# ST_LINK_V2-1.net
KiCad netlist of a schematic drawn in Altium Designer
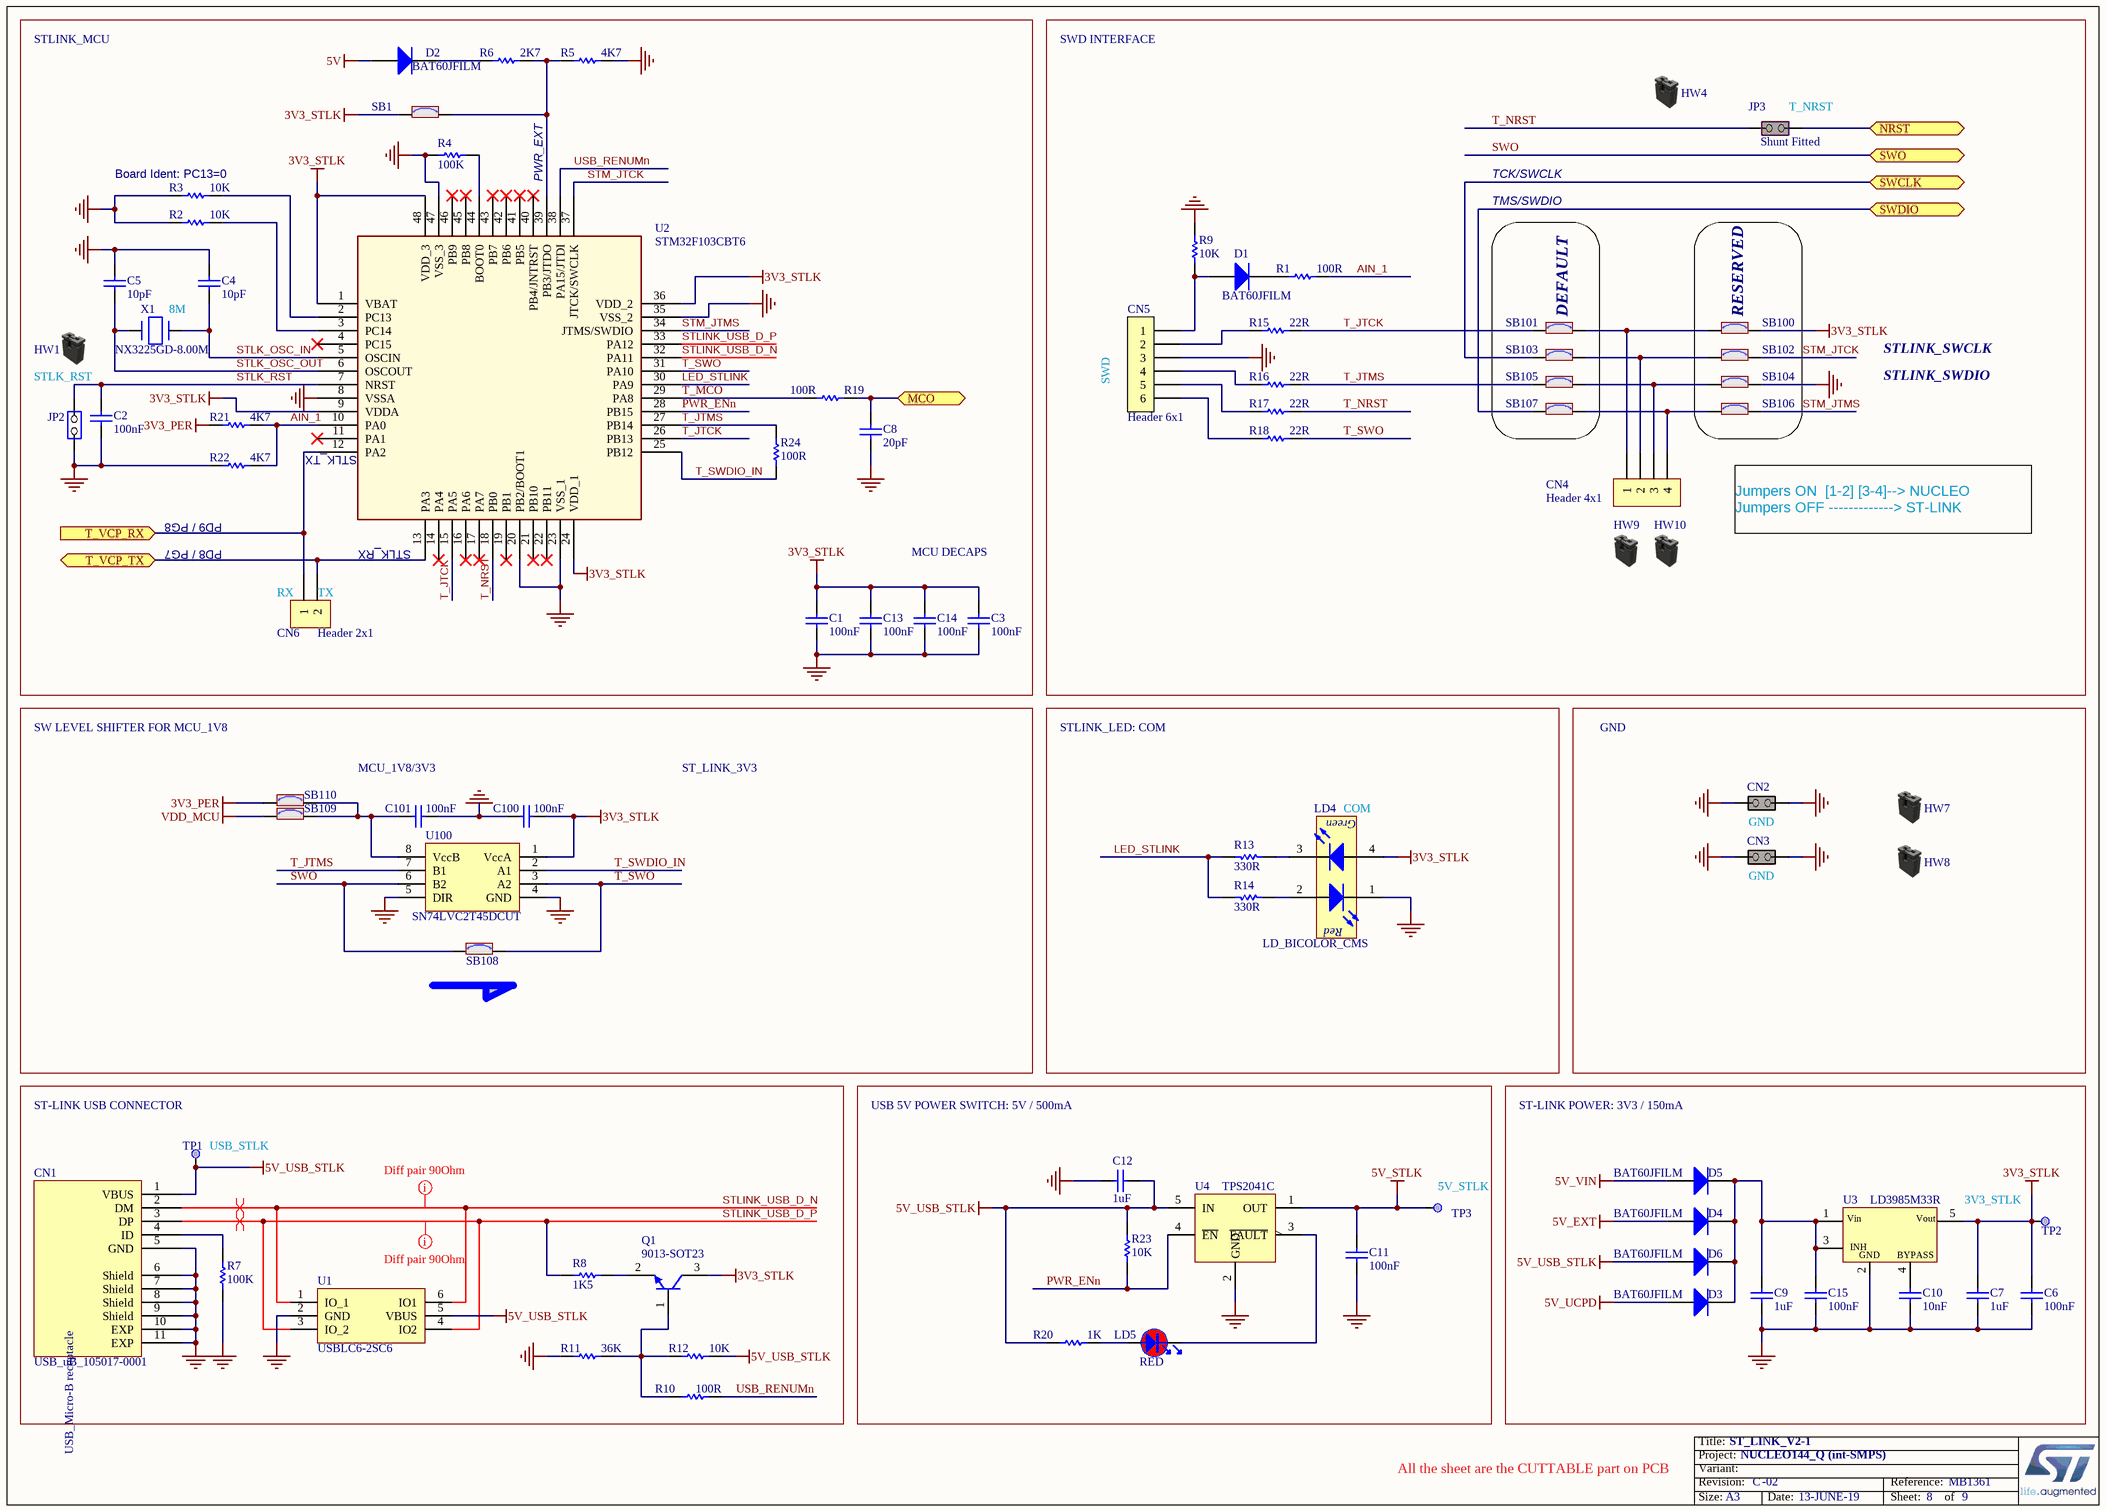
[diagram p0: ST_LINK_V2-1.SchDoc]

(export (version "E")
  (design (tool "Eeschema 10.0.6"))
  (components
    (comp (ref "C1")
      (value "100nF")
      (footprint "C0603")
      (description "Capacitor, MLCC, 100nF, 16V, X7R, 10%, 0603, T=0,8mm")
      (fields
        (field (name "INTERNAL_PART_NUMBER") "MCD-00211")
        (field (name "MANUFACTURER_PART_NUMBER") "CC0603KRX7R7BB104")
        (field (name "PROVIDED_BY") "Subcon")
      )
      (libsource (lib "MCD_PARTS_database") (part "Capacitor"))
    )
    (comp (ref "C2")
      (value "100nF")
      (footprint "C0603")
      (description "Capacitor, MLCC, 100nF, 16V, X7R, 10%, 0603, T=0,8mm")
      (fields
        (field (name "INTERNAL_PART_NUMBER") "MCD-00211")
        (field (name "MANUFACTURER_PART_NUMBER") "CC0603KRX7R7BB104")
        (field (name "PROVIDED_BY") "Subcon")
      )
      (libsource (lib "MCD_PARTS_database") (part "Capacitor"))
    )
    (comp (ref "C3")
      (value "100nF")
      (footprint "C0603")
      (description "Capacitor, MLCC, 100nF, 16V, X7R, 10%, 0603, T=0,8mm")
      (fields
        (field (name "INTERNAL_PART_NUMBER") "MCD-00211")
        (field (name "MANUFACTURER_PART_NUMBER") "CC0603KRX7R7BB104")
        (field (name "PROVIDED_BY") "Subcon")
      )
      (libsource (lib "MCD_PARTS_database") (part "Capacitor"))
    )
    (comp (ref "C4")
      (value "10pF")
      (footprint "C0402")
      (description "Capacitor, MLCC, 10pF, 50V, NPO, 5%, 0402, T=0,5mm")
      (fields
        (field (name "INTERNAL_PART_NUMBER") "MCD-00015")
        (field (name "MANUFACTURER_PART_NUMBER") "CC0402JRNPO9BN100")
        (field (name "PROVIDED_BY") "subcon")
      )
      (libsource (lib "MCD_PARTS_database") (part "Capacitor"))
    )
    (comp (ref "C5")
      (value "10pF")
      (footprint "C0402")
      (description "Capacitor, MLCC, 10pF, 50V, NPO, 5%, 0402, T=0,5mm")
      (fields
        (field (name "INTERNAL_PART_NUMBER") "MCD-00015")
        (field (name "MANUFACTURER_PART_NUMBER") "CC0402JRNPO9BN100")
        (field (name "PROVIDED_BY") "subcon")
      )
      (libsource (lib "MCD_PARTS_database") (part "Capacitor"))
    )
    (comp (ref "C6")
      (value "100nF")
      (footprint "C0603")
      (description "Capacitor, MLCC, 100nF, 16V, X7R, 10%, 0603, T=0,8mm")
      (fields
        (field (name "INTERNAL_PART_NUMBER") "MCD-00211")
        (field (name "MANUFACTURER_PART_NUMBER") "CC0603KRX7R7BB104")
        (field (name "PROVIDED_BY") "Subcon")
      )
      (libsource (lib "MCD_PARTS_database") (part "Capacitor"))
    )
    (comp (ref "C7")
      (value "1uF")
      (footprint "C0603")
      (description "Capacitor, MLCC, 1uF, 16V, X5R, 10%, 0603, T=0,8mm")
      (fields
        (field (name "INTERNAL_PART_NUMBER") "MCD-00010")
        (field (name "MANUFACTURER_PART_NUMBER") "CC0603KRX5R7BB105")
        (field (name "PROVIDED_BY") "SUBCO")
      )
      (libsource (lib "MCD_PARTS_database") (part "Capacitor"))
    )
    (comp (ref "C8")
      (value "20pF")
      (footprint "C0603")
      (description "Capacitor, MLCC, 20pF, 50V, NPO, 5%, 0603, T=0,8mm")
      (fields
        (field (name "INTERNAL_PART_NUMBER") "MCD-00638")
        (field (name "MANUFACTURER_PART_NUMBER") "CC0603JRNPO9BN200")
        (field (name "PROVIDED_BY") "Subcon")
      )
      (libsource (lib "MCD_PARTS_database") (part "Capacitor"))
    )
    (comp (ref "C9")
      (value "1uF")
      (footprint "C0603")
      (description "Capacitor, MLCC, 1uF, 16V, X5R, 10%, 0603, T=0,8mm")
      (fields
        (field (name "INTERNAL_PART_NUMBER") "MCD-00010")
        (field (name "MANUFACTURER_PART_NUMBER") "CC0603KRX5R7BB105")
        (field (name "PROVIDED_BY") "Subcon")
      )
      (libsource (lib "MCD_PARTS_database") (part "Capacitor"))
    )
    (comp (ref "C10")
      (value "10nF")
      (footprint "C0603")
      (description "Capacitor, MLCC, 10nF, 50V, X7R, 10%, 0603, T=0.8mm")
      (fields
        (field (name "INTERNAL_PART_NUMBER") "MCD-00017")
        (field (name "MANUFACTURER_PART_NUMBER") "CC0603KRX7R9BB103")
        (field (name "PROVIDED_BY") "Subcon")
      )
      (libsource (lib "MCD_PARTS_database") (part "Capacitor"))
    )
    (comp (ref "C11")
      (value "100nF")
      (footprint "C0603")
      (description "Capacitor, MLCC, 100nF, 16V, X7R, 10%, 0603, T=0,8mm")
      (fields
        (field (name "INTERNAL_PART_NUMBER") "MCD-00211")
        (field (name "MANUFACTURER_PART_NUMBER") "CC0603KRX7R7BB104")
        (field (name "PROVIDED_BY") "Subcon")
      )
      (libsource (lib "MCD_PARTS_database") (part "Capacitor"))
    )
    (comp (ref "C12")
      (value "1uF")
      (footprint "C0603")
      (description "Capacitor, MLCC, 1uF, 16V, X5R, 10%, 0603, T=0,8mm")
      (fields
        (field (name "INTERNAL_PART_NUMBER") "MCD-00010")
        (field (name "MANUFACTURER_PART_NUMBER") "CC0603KRX5R7BB105")
        (field (name "PROVIDED_BY") "SUBCO")
      )
      (libsource (lib "MCD_PARTS_database") (part "Capacitor"))
    )
    (comp (ref "C13")
      (value "100nF")
      (footprint "C0603")
      (description "Capacitor, MLCC, 100nF, 16V, X7R, 10%, 0603, T=0,8mm")
      (fields
        (field (name "INTERNAL_PART_NUMBER") "MCD-00211")
        (field (name "MANUFACTURER_PART_NUMBER") "CC0603KRX7R7BB104")
        (field (name "PROVIDED_BY") "Subcon")
      )
      (libsource (lib "MCD_PARTS_database") (part "Capacitor"))
    )
    (comp (ref "C14")
      (value "100nF")
      (footprint "C0603")
      (description "Capacitor, MLCC, 100nF, 16V, X7R, 10%, 0603, T=0,8mm")
      (fields
        (field (name "INTERNAL_PART_NUMBER") "MCD-00211")
        (field (name "MANUFACTURER_PART_NUMBER") "CC0603KRX7R7BB104")
        (field (name "PROVIDED_BY") "Subcon")
      )
      (libsource (lib "MCD_PARTS_database") (part "Capacitor"))
    )
    (comp (ref "C15")
      (value "100nF")
      (footprint "C0603")
      (description "Capacitor, MLCC, 100nF, 16V, X7R, 10%, 0603, T=0,8mm")
      (fields
        (field (name "INTERNAL_PART_NUMBER") "MCD-00211")
        (field (name "MANUFACTURER_PART_NUMBER") "CC0603KRX7R7BB104")
        (field (name "PROVIDED_BY") "Subcon")
      )
      (libsource (lib "MCD_PARTS_database") (part "Capacitor"))
    )
    (comp (ref "C100")
      (value "100nF")
      (footprint "C0603")
      (description "Capacitor, MLCC, 100nF, 16V, X7R, 10%, 0603, T=0,8mm")
      (fields
        (field (name "INTERNAL_PART_NUMBER") "MCD-00211")
        (field (name "MANUFACTURER_PART_NUMBER") "CC0603KRX7R7BB104")
        (field (name "PROVIDED_BY") "Subcon")
      )
      (libsource (lib "MCD_PARTS_database") (part "Capacitor"))
    )
    (comp (ref "C101")
      (value "100nF")
      (footprint "C0603")
      (description "Capacitor, MLCC, 100nF, 16V, X7R, 10%, 0603, T=0,8mm")
      (fields
        (field (name "INTERNAL_PART_NUMBER") "MCD-00211")
        (field (name "MANUFACTURER_PART_NUMBER") "CC0603KRX7R7BB104")
        (field (name "PROVIDED_BY") "Subcon")
      )
      (libsource (lib "MCD_PARTS_database") (part "Capacitor"))
    )
    (comp (ref "CN1")
      (value "USB_uB_105017-0001")
      (footprint "CON_USBMICROB_MOLEX_105017-0001_H2P90")
      (description "USB-MICRO-B, 0.65mm, RA, SMT, Bottom Mount,")
      (fields
        (field (name "INTERNAL_PART_NUMBER") "MCD-00028")
        (field (name "MANUFACTURER_PART_NUMBER") "1050170001")
        (field (name "PROVIDED_BY") "Subcon")
      )
      (libsource (lib "MCD_PARTS_database") (part "USB_uB_105017.0001"))
    )
    (comp (ref "CN2")
      (value "~")
      (footprint "CON_SAMTEC_TSW-102-09-X-S")
      (description "Header, 2x1, 2,54mm, VR, TH, Height 5.84mm/10.16mm")
      (fields
        (field (name "INTERNAL_PART_NUMBER") "MCD-00214")
        (field (name "MANUFACTURER_PART_NUMBER") "TSW-102-09-x-S")
        (field (name "PROVIDED_BY") "Subcon")
      )
      (libsource (lib "MCD_PARTS_database") (part "Jumper_Header 2x1"))
    )
    (comp (ref "CN3")
      (value "~")
      (footprint "CON_SAMTEC_TSW-102-09-X-S")
      (description "Header, 2x1, 2,54mm, VR, TH, Height 5.84mm/10.16mm")
      (fields
        (field (name "INTERNAL_PART_NUMBER") "MCD-00214")
        (field (name "MANUFACTURER_PART_NUMBER") "TSW-102-09-x-S")
        (field (name "PROVIDED_BY") "Subcon")
      )
      (libsource (lib "MCD_PARTS_database") (part "Jumper_Header 2x1"))
    )
    (comp (ref "CN4")
      (value "Header 4x1")
      (footprint "CON_SAMTEC_TSW-104-07-G-S")
      (description "Header, 4x1, 2,54mm, VR, TH, Height 5.84mm/2.54mm")
      (fields
        (field (name "INTERNAL_PART_NUMBER") "MCD-00029")
        (field (name "MANUFACTURER_PART_NUMBER") "TSW-104-07-x-S")
        (field (name "PROVIDED_BY") "SUBCO")
      )
      (libsource (lib "MCD_PARTS_database") (part "Header 4x1"))
    )
    (comp (ref "CN5")
      (value "Header 6x1")
      (footprint "CON_SAMTEC_TSW-106-07-X-S")
      (description "Header, 6x1, 2,54mm, VR, TH, Height 5.84mm/2.54mm")
      (fields
        (field (name "INTERNAL_PART_NUMBER") "MCD-00212")
        (field (name "MANUFACTURER_PART_NUMBER") "TSW-106-07-x-S")
        (field (name "PROVIDED_BY") "Subcon")
      )
      (libsource (lib "MCD_PARTS_database") (part "Header 6x1"))
    )
    (comp (ref "CN6")
      (value "Header 2x1")
      (footprint "CON_SAMTEC_TSW-102-07-G-S")
      (description "Header, 2x1, 2,54mm, VR, TH, Height 5.84mm/2.54mm")
      (fields
        (field (name "INTERNAL_PART_NUMBER") "MCD-00032")
        (field (name "MANUFACTURER_PART_NUMBER") "TSW-102-07-x-S")
        (field (name "PROVIDED_BY") "Subcon")
      )
      (libsource (lib "MCD_PARTS_database") (part "Header 2x1"))
    )
    (comp (ref "D1")
      (value "BAT60JFILM")
      (footprint "DIO_SOD323")
      (fields
        (field (name "INTERNAL_PART_NUMBER") "MCD-00034")
        (field (name "MANUFACTURER") "STMICROELECTRONICS")
        (field (name "PROVIDED_BY") "Subcon")
      )
      (libsource (lib "MCD_PARTS_database") (part "BAT60JFILM"))
    )
    (comp (ref "D2")
      (value "BAT60JFILM")
      (footprint "DIO_SOD323")
      (fields
        (field (name "INTERNAL_PART_NUMBER") "MCD-00034")
        (field (name "MANUFACTURER") "STMICROELECTRONICS")
        (field (name "PROVIDED_BY") "Subcon")
      )
      (libsource (lib "MCD_PARTS_database") (part "BAT60JFILM"))
    )
    (comp (ref "D3")
      (value "BAT60JFILM")
      (footprint "DIO_SOD323")
      (fields
        (field (name "INTERNAL_PART_NUMBER") "MCD-00034")
        (field (name "MANUFACTURER") "STMICROELECTRONICS")
        (field (name "PROVIDED_BY") "Subcon")
      )
      (libsource (lib "MCD_PARTS_database") (part "BAT60JFILM"))
    )
    (comp (ref "D4")
      (value "BAT60JFILM")
      (footprint "DIO_SOD323")
      (fields
        (field (name "INTERNAL_PART_NUMBER") "MCD-00034")
        (field (name "MANUFACTURER") "STMICROELECTRONICS")
        (field (name "PROVIDED_BY") "Subcon")
      )
      (libsource (lib "MCD_PARTS_database") (part "BAT60JFILM"))
    )
    (comp (ref "D5")
      (value "BAT60JFILM")
      (footprint "DIO_SOD323")
      (fields
        (field (name "INTERNAL_PART_NUMBER") "MCD-00034")
        (field (name "MANUFACTURER") "STMICROELECTRONICS")
        (field (name "PROVIDED_BY") "Subcon")
      )
      (libsource (lib "MCD_PARTS_database") (part "BAT60JFILM"))
    )
    (comp (ref "D6")
      (value "BAT60JFILM")
      (footprint "DIO_SOD323")
      (fields
        (field (name "INTERNAL_PART_NUMBER") "MCD-00034")
        (field (name "MANUFACTURER") "STMICROELECTRONICS")
        (field (name "PROVIDED_BY") "Subcon")
      )
      (libsource (lib "MCD_PARTS_database") (part "BAT60JFILM"))
    )
    (comp (ref "HW1")
      (value "~")
      (description "SHUNT 2.54mm BLACK")
      (fields
        (field (name "INTERNAL_PART_NUMBER") "MCD-00043")
        (field (name "MANUFACTURER_PART_NUMBER") "SNT-100-BK-G")
        (field (name "PROVIDED_BY") "Subcon")
      )
      (libsource (lib "MCD_PARTS_database") (part "Shunt Black 2.54mm"))
    )
    (comp (ref "HW4")
      (value "~")
      (description "SHUNT 2.54mm BLACK")
      (fields
        (field (name "INTERNAL_PART_NUMBER") "MCD-00043")
        (field (name "MANUFACTURER_PART_NUMBER") "SNT-100-BK-G")
        (field (name "PROVIDED_BY") "Subcon")
      )
      (libsource (lib "MCD_PARTS_database") (part "Shunt Black 2.54mm"))
    )
    (comp (ref "HW7")
      (value "~")
      (description "SHUNT 2.54mm BLACK")
      (fields
        (field (name "INTERNAL_PART_NUMBER") "MCD-00043")
        (field (name "MANUFACTURER_PART_NUMBER") "SNT-100-BK-G")
        (field (name "PROVIDED_BY") "Subcon")
      )
      (libsource (lib "MCD_PARTS_database") (part "Shunt Black 2.54mm"))
    )
    (comp (ref "HW8")
      (value "~")
      (description "SHUNT 2.54mm BLACK")
      (fields
        (field (name "INTERNAL_PART_NUMBER") "MCD-00043")
        (field (name "MANUFACTURER_PART_NUMBER") "SNT-100-BK-G")
        (field (name "PROVIDED_BY") "Subcon")
      )
      (libsource (lib "MCD_PARTS_database") (part "Shunt Black 2.54mm"))
    )
    (comp (ref "HW9")
      (value "~")
      (description "SHUNT 2.54mm BLACK")
      (fields
        (field (name "INTERNAL_PART_NUMBER") "MCD-00043")
        (field (name "MANUFACTURER_PART_NUMBER") "SNT-100-BK-G")
        (field (name "PROVIDED_BY") "Subcon")
      )
      (libsource (lib "MCD_PARTS_database") (part "Shunt Black 2.54mm"))
    )
    (comp (ref "HW10")
      (value "~")
      (description "SHUNT 2.54mm BLACK")
      (fields
        (field (name "INTERNAL_PART_NUMBER") "MCD-00043")
        (field (name "MANUFACTURER_PART_NUMBER") "SNT-100-BK-G")
        (field (name "PROVIDED_BY") "Subcon")
      )
      (libsource (lib "MCD_PARTS_database") (part "Shunt Black 2.54mm"))
    )
    (comp (ref "JP2")
      (value "~")
      (footprint "CON_SAMTEC_TSW-102-07-G-S")
      (description "Header, 2x1, 2,54mm, VR, TH, Height 5.84mm/2.54mm")
      (fields
        (field (name "INTERNAL_PART_NUMBER") "MCD-00045")
        (field (name "MANUFACTURER_PART_NUMBER") "TSW-102-07-x-S")
        (field (name "PROVIDED_BY") "Subcon")
      )
      (libsource (lib "MCD_PARTS_database") (part "Jumper_Header 2x1"))
    )
    (comp (ref "JP3")
      (value "Shunt Fitted")
      (footprint "CON_SAMTEC_TSW-102-07-G-S")
      (description "Header, 2x1, 2,54mm, VR, TH, Height 5.84mm/2.54mm - Shunt Fitted by default")
      (fields
        (field (name "INTERNAL_PART_NUMBER") "MCD-00683")
        (field (name "MANUFACTURER_PART_NUMBER") "TSW-102-07-x-S")
        (field (name "PROVIDED_BY") "Subcon")
      )
      (libsource (lib "MCD_PARTS_database") (part "Jumper_Header 2x1 Fitted"))
    )
    (comp (ref "LD4")
      (value "LD_BICOLOR_CMS")
      (footprint "LED_BI-GR_HSMF-A201-A00J1")
      (description "LED Bicolor")
      (fields
        (field (name "INTERNAL_PART_NUMBER") "MCD-00051")
        (field (name "MANUFACTURER_PART_NUMBER") "HSMF-A201-A00J1")
        (field (name "PROVIDED_BY") "Subcon")
      )
      (libsource (lib "MCD_PARTS_database") (part "LD_BICOLOR_CMS"))
    )
    (comp (ref "LD5")
      (value "RED")
      (footprint "LED_0603_RED_H0P4")
      (description "LED, Red, 0603")
      (fields
        (field (name "INTERNAL_PART_NUMBER") "MCD-00322")
        (field (name "MANUFACTURER_PART_NUMBER") "19-217/R6C-AL1M2VY/3T")
        (field (name "PROVIDED_BY") "Subcon")
      )
      (libsource (lib "MCD_PARTS_database") (part "LED_red"))
    )
    (comp (ref "Q1")
      (value "9013-SOT23")
      (footprint "NPN_SOT23")
      (description "NPN Bipolar Transistor")
      (fields
        (field (name "INTERNAL_PART_NUMBER") "MCD-00073")
        (field (name "MANUFACTURER_PART_NUMBER") "BSR14")
        (field (name "PROVIDED_BY") "Subcon")
      )
      (libsource (lib "MCD_PARTS_database") (part "9013-SOT23"))
    )
    (comp (ref "R1")
      (value "100R")
      (footprint "R0603")
      (description "Resistor,100R,0603,1%,1/10W")
      (fields
        (field (name "INTERNAL_PART_NUMBER") "MCD-00224")
        (field (name "MANUFACTURER_PART_NUMBER") "RC0603FR-07100RL")
        (field (name "PROVIDED_BY") "Subcon")
      )
      (libsource (lib "MCD_PARTS_database") (part "Resistor"))
    )
    (comp (ref "R2")
      (value "10K")
      (footprint "R0603")
      (description "Resistor,10K,0603,1%,1/10W")
      (fields
        (field (name "INTERNAL_PART_NUMBER") "MCD-00220")
        (field (name "MANUFACTURER_PART_NUMBER") "RC0603FR-0710KL")
        (field (name "PROVIDED_BY") "Subcon")
      )
      (libsource (lib "MCD_PARTS_database") (part "Resistor"))
    )
    (comp (ref "R3")
      (value "10K")
      (footprint "R0603")
      (description "Resistor,10K,0603,1%,1/10W")
      (fields
        (field (name "INTERNAL_PART_NUMBER") "MCD-00220")
        (field (name "MANUFACTURER_PART_NUMBER") "RC0603FR-0710KL")
        (field (name "PROVIDED_BY") "Subcon")
      )
      (libsource (lib "MCD_PARTS_database") (part "Resistor"))
    )
    (comp (ref "R4")
      (value "100K")
      (footprint "R0603")
      (description "Resistor,100K,0603,1%,1/10W")
      (fields
        (field (name "INTERNAL_PART_NUMBER") "MCD-00223")
        (field (name "MANUFACTURER_PART_NUMBER") "RC0603FR-07100KL")
        (field (name "PROVIDED_BY") "Subcon")
      )
      (libsource (lib "MCD_PARTS_database") (part "Resistor"))
    )
    (comp (ref "R5")
      (value "4K7")
      (footprint "R0603")
      (description "Resistor,4K7,0603,1%,1/10W")
      (fields
        (field (name "INTERNAL_PART_NUMBER") "MCD-00219")
        (field (name "MANUFACTURER_PART_NUMBER") "RC0603FR-074K7L")
        (field (name "PROVIDED_BY") "Subcon")
      )
      (libsource (lib "MCD_PARTS_database") (part "Resistor"))
    )
    (comp (ref "R6")
      (value "2K7")
      (footprint "R0603")
      (description "Resistor,2K7,0603,1%,1/10W")
      (fields
        (field (name "INTERNAL_PART_NUMBER") "MCD-00218")
        (field (name "MANUFACTURER_PART_NUMBER") "RC0603FR-072K7L")
        (field (name "PROVIDED_BY") "Subcon")
      )
      (libsource (lib "MCD_PARTS_database") (part "Resistor"))
    )
    (comp (ref "R7")
      (value "100K")
      (footprint "R0603")
      (description "Resistor,100K,0603,1%,1/10W")
      (fields
        (field (name "INTERNAL_PART_NUMBER") "MCD-00223")
        (field (name "MANUFACTURER_PART_NUMBER") "RC0603FR-07100KL")
        (field (name "PROVIDED_BY") "Subcon")
      )
      (libsource (lib "MCD_PARTS_database") (part "Resistor"))
    )
    (comp (ref "R8")
      (value "1K5")
      (footprint "R0603")
      (description "Resistor,1K5,0603,1%,1/10W")
      (fields
        (field (name "INTERNAL_PART_NUMBER") "MCD-00217")
        (field (name "MANUFACTURER_PART_NUMBER") "RC0603FR-071K5L")
        (field (name "PROVIDED_BY") "Subcon")
      )
      (libsource (lib "MCD_PARTS_database") (part "Resistor"))
    )
    (comp (ref "R9")
      (value "10K")
      (footprint "R0603")
      (description "Resistor,10K,0603,1%,1/10W")
      (fields
        (field (name "INTERNAL_PART_NUMBER") "MCD-00220")
        (field (name "MANUFACTURER_PART_NUMBER") "RC0603FR-0710KL")
        (field (name "PROVIDED_BY") "Subcon")
      )
      (libsource (lib "MCD_PARTS_database") (part "Resistor"))
    )
    (comp (ref "R10")
      (value "100R")
      (footprint "R0603")
      (description "Resistor,100R,0603,1%,1/10W")
      (fields
        (field (name "INTERNAL_PART_NUMBER") "MCD-00224")
        (field (name "MANUFACTURER_PART_NUMBER") "RC0603FR-07100RL")
        (field (name "PROVIDED_BY") "Subcon")
      )
      (libsource (lib "MCD_PARTS_database") (part "Resistor"))
    )
    (comp (ref "R11")
      (value "36K")
      (footprint "R0603")
      (description "Resistor,36K,0603,1%,1/10W")
      (fields
        (field (name "INTERNAL_PART_NUMBER") "MCD-00221")
        (field (name "MANUFACTURER_PART_NUMBER") "RC0603FR-0736KL")
        (field (name "PROVIDED_BY") "Subcon")
      )
      (libsource (lib "MCD_PARTS_database") (part "Resistor"))
    )
    (comp (ref "R12")
      (value "10K")
      (footprint "R0603")
      (description "Resistor,10K,0603,1%,1/10W")
      (fields
        (field (name "INTERNAL_PART_NUMBER") "MCD-00220")
        (field (name "MANUFACTURER_PART_NUMBER") "RC0603FR-0710KL")
        (field (name "PROVIDED_BY") "Subcon")
      )
      (libsource (lib "MCD_PARTS_database") (part "Resistor"))
    )
    (comp (ref "R13")
      (value "330R")
      (footprint "R0603")
      (description "Resistor,330R,0603,1%,1/10W")
      (fields
        (field (name "INTERNAL_PART_NUMBER") "MCD-00197")
        (field (name "MANUFACTURER_PART_NUMBER") "RC0603FR-07330RL")
        (field (name "PROVIDED_BY") "Subcon")
      )
      (libsource (lib "MCD_PARTS_database") (part "Resistor"))
    )
    (comp (ref "R14")
      (value "330R")
      (footprint "R0603")
      (description "Resistor,330R,0603,1%,1/10W")
      (fields
        (field (name "INTERNAL_PART_NUMBER") "MCD-00197")
        (field (name "MANUFACTURER_PART_NUMBER") "RC0603FR-07330RL")
        (field (name "PROVIDED_BY") "Subcon")
      )
      (libsource (lib "MCD_PARTS_database") (part "Resistor"))
    )
    (comp (ref "R15")
      (value "22R")
      (footprint "R0603")
      (description "Resistor,22R,0603,1%,1/10W")
      (fields
        (field (name "INTERNAL_PART_NUMBER") "MCD-00190")
        (field (name "MANUFACTURER_PART_NUMBER") "RC0603FR-0722RL")
        (field (name "PROVIDED_BY") "Subcon")
      )
      (libsource (lib "MCD_PARTS_database") (part "Resistor"))
    )
    (comp (ref "R16")
      (value "22R")
      (footprint "R0603")
      (description "Resistor,22R,0603,1%,1/10W")
      (fields
        (field (name "INTERNAL_PART_NUMBER") "MCD-00190")
        (field (name "MANUFACTURER_PART_NUMBER") "RC0603FR-0722RL")
        (field (name "PROVIDED_BY") "Subcon")
      )
      (libsource (lib "MCD_PARTS_database") (part "Resistor"))
    )
    (comp (ref "R17")
      (value "22R")
      (footprint "R0603")
      (description "Resistor,22R,0603,1%,1/10W")
      (fields
        (field (name "INTERNAL_PART_NUMBER") "MCD-00190")
        (field (name "MANUFACTURER_PART_NUMBER") "RC0603FR-0722RL")
        (field (name "PROVIDED_BY") "Subcon")
      )
      (libsource (lib "MCD_PARTS_database") (part "Resistor"))
    )
    (comp (ref "R18")
      (value "22R")
      (footprint "R0603")
      (description "Resistor,22R,0603,1%,1/10W")
      (fields
        (field (name "INTERNAL_PART_NUMBER") "MCD-00190")
        (field (name "MANUFACTURER_PART_NUMBER") "RC0603FR-0722RL")
        (field (name "PROVIDED_BY") "Subcon")
      )
      (libsource (lib "MCD_PARTS_database") (part "Resistor"))
    )
    (comp (ref "R19")
      (value "100R")
      (footprint "R0603")
      (description "Resistor,100R,0603,1%,1/10W")
      (fields
        (field (name "INTERNAL_PART_NUMBER") "MCD-00224")
        (field (name "MANUFACTURER_PART_NUMBER") "RC0603FR-07100RL")
        (field (name "PROVIDED_BY") "Subcon")
      )
      (libsource (lib "MCD_PARTS_database") (part "Resistor"))
    )
    (comp (ref "R20")
      (value "1K")
      (footprint "R0603")
      (description "Resistor,1K,0603,1%,1/10W")
      (fields
        (field (name "INTERNAL_PART_NUMBER") "MCD-00070")
        (field (name "MANUFACTURER_PART_NUMBER") "RC0603FR-071KL")
        (field (name "PROVIDED_BY") "Subcon")
      )
      (libsource (lib "MCD_PARTS_database") (part "Resistor"))
    )
    (comp (ref "R21")
      (value "4K7")
      (footprint "R0603")
      (description "Resistor,4K7,0603,1%,1/10W")
      (fields
        (field (name "INTERNAL_PART_NUMBER") "MCD-00219")
        (field (name "MANUFACTURER_PART_NUMBER") "RC0603FR-074K7L")
        (field (name "PROVIDED_BY") "Subcon")
      )
      (libsource (lib "MCD_PARTS_database") (part "Resistor"))
    )
    (comp (ref "R22")
      (value "4K7")
      (footprint "R0603")
      (description "Resistor,4K7,0603,1%,1/10W")
      (fields
        (field (name "INTERNAL_PART_NUMBER") "MCD-00219")
        (field (name "MANUFACTURER_PART_NUMBER") "RC0603FR-074K7L")
        (field (name "PROVIDED_BY") "Subcon")
      )
      (libsource (lib "MCD_PARTS_database") (part "Resistor"))
    )
    (comp (ref "R23")
      (value "10K")
      (footprint "R0603")
      (description "Resistor,10K,0603,1%,1/10W")
      (fields
        (field (name "INTERNAL_PART_NUMBER") "MCD-00220")
        (field (name "MANUFACTURER_PART_NUMBER") "RC0603FR-0710KL")
        (field (name "PROVIDED_BY") "Subcon")
      )
      (libsource (lib "MCD_PARTS_database") (part "Resistor"))
    )
    (comp (ref "R24")
      (value "100R")
      (footprint "R0603")
      (description "Resistor,100R,0603,1%,1/10W")
      (fields
        (field (name "INTERNAL_PART_NUMBER") "MCD-00224")
        (field (name "MANUFACTURER_PART_NUMBER") "RC0603FR-07100RL")
        (field (name "PROVIDED_BY") "Subcon")
      )
      (libsource (lib "MCD_PARTS_database") (part "Resistor"))
    )
    (comp (ref "SB1")
      (value "~")
      (footprint "SOLDER-BRIDGE_R0603-0R")
      (description "Solder Bridge ON")
      (fields (field (name "INTERNAL_PART_NUMBER") "MCD-00071") (field (name "PROVIDED_BY") "Subcon"))
      (libsource (lib "MCD_PARTS_database") (part "SB_ON"))
    )
    (comp (ref "SB100")
      (value "~")
      (footprint "SOLDER-BRIDGE_R0603-0R")
      (description "Solder Bridge ON")
      (fields (field (name "INTERNAL_PART_NUMBER") "MCD-00071") (field (name "PROVIDED_BY") "Subcon"))
      (libsource (lib "MCD_PARTS_database") (part "SB_ON"))
    )
    (comp (ref "SB101")
      (value "~")
      (footprint "SOLDER-BRIDGE_R0603-0R")
      (description "Solder Bridge ON")
      (fields (field (name "INTERNAL_PART_NUMBER") "MCD-00071") (field (name "PROVIDED_BY") "Subcon"))
      (libsource (lib "MCD_PARTS_database") (part "SB_ON"))
    )
    (comp (ref "SB102")
      (value "~")
      (footprint "SOLDER-BRIDGE_R0603-0R")
      (description "Solder Bridge ON")
      (fields (field (name "INTERNAL_PART_NUMBER") "MCD-00071") (field (name "PROVIDED_BY") "Subcon"))
      (libsource (lib "MCD_PARTS_database") (part "SB_ON"))
    )
    (comp (ref "SB103")
      (value "~")
      (footprint "SOLDER-BRIDGE_R0603-0R")
      (description "Solder Bridge ON")
      (fields (field (name "INTERNAL_PART_NUMBER") "MCD-00071") (field (name "PROVIDED_BY") "Subcon"))
      (libsource (lib "MCD_PARTS_database") (part "SB_ON"))
    )
    (comp (ref "SB104")
      (value "~")
      (footprint "SOLDER-BRIDGE_R0603-0R")
      (description "Solder Bridge ON")
      (fields (field (name "INTERNAL_PART_NUMBER") "MCD-00071") (field (name "PROVIDED_BY") "Subcon"))
      (libsource (lib "MCD_PARTS_database") (part "SB_ON"))
    )
    (comp (ref "SB105")
      (value "~")
      (footprint "SOLDER-BRIDGE_R0603-0R")
      (description "Solder Bridge ON")
      (fields (field (name "INTERNAL_PART_NUMBER") "MCD-00071") (field (name "PROVIDED_BY") "Subcon"))
      (libsource (lib "MCD_PARTS_database") (part "SB_ON"))
    )
    (comp (ref "SB106")
      (value "~")
      (footprint "SOLDER-BRIDGE_R0603-0R")
      (description "Solder Bridge ON")
      (fields (field (name "INTERNAL_PART_NUMBER") "MCD-00071") (field (name "PROVIDED_BY") "Subcon"))
      (libsource (lib "MCD_PARTS_database") (part "SB_ON"))
    )
    (comp (ref "SB107")
      (value "~")
      (footprint "SOLDER-BRIDGE_R0603-0R")
      (description "Solder Bridge ON")
      (fields (field (name "INTERNAL_PART_NUMBER") "MCD-00071") (field (name "PROVIDED_BY") "Subcon"))
      (libsource (lib "MCD_PARTS_database") (part "SB_ON"))
    )
    (comp (ref "SB108")
      (value "~")
      (footprint "SOLDER-BRIDGE_R0603-0R")
      (description "Solder Bridge ON")
      (fields (field (name "INTERNAL_PART_NUMBER") "MCD-00071") (field (name "PROVIDED_BY") "Subcon"))
      (libsource (lib "") (part "SB_ON_1"))
    )
    (comp (ref "SB109")
      (value "~")
      (footprint "SOLDER-BRIDGE_R0603-0R")
      (description "Solder Bridge ON")
      (fields (field (name "INTERNAL_PART_NUMBER") "MCD-00071") (field (name "PROVIDED_BY") "Subcon"))
      (libsource (lib "") (part "SB_ON_1"))
    )
    (comp (ref "SB110")
      (value "~")
      (footprint "SOLDER-BRIDGE_R0603-0R")
      (description "Solder Bridge ON")
      (fields (field (name "INTERNAL_PART_NUMBER") "MCD-00071") (field (name "PROVIDED_BY") "Subcon"))
      (libsource (lib "") (part "SB_ON_1"))
    )
    (comp (ref "TP1")
      (value "~")
      (footprint "TP_SMD_1MM")
      (description "Test Point 1mm")
      (fields
        (field (name "INTERNAL_PART_NUMBER") "MCD-00074")
        (field (name "MANUFACTURER_PART_NUMBER") "n/a")
      )
      (libsource (lib "") (part "Test Point_1"))
    )
    (comp (ref "TP2")
      (value "~")
      (footprint "TP_SMD_1MM")
      (description "Test Point 1mm")
      (fields
        (field (name "INTERNAL_PART_NUMBER") "MCD-00074")
        (field (name "MANUFACTURER_PART_NUMBER") "n/a")
      )
      (libsource (lib "MCD_PARTS_database") (part "Test Point"))
    )
    (comp (ref "TP3")
      (value "~")
      (footprint "TP_SMD_1MM")
      (description "Test Point 1mm")
      (fields
        (field (name "INTERNAL_PART_NUMBER") "MCD-00074")
        (field (name "MANUFACTURER_PART_NUMBER") "n/a")
      )
      (libsource (lib "MCD_PARTS_database") (part "Test Point"))
    )
    (comp (ref "U1")
      (value "USBLC6-2SC6")
      (footprint "ESD_SOT23-6L")
      (description "Very low capacitance ESD protection")
      (fields
        (field (name "INTERNAL_PART_NUMBER") "MCD-00163")
        (field (name "MANUFACTURER") "STMICROELECTRONICS")
        (field (name "PROVIDED_BY") "Subcon")
      )
      (libsource (lib "MCD_PARTS_database") (part "USBLC6-2SC6"))
    )
    (comp (ref "U2")
      (value "STM32F103CBT6")
      (footprint "ICC_LQFP48_7X7_P050")
      (description "Medium-density performance line ARM-based 32-bit MCU with 128KB Flash")
      (fields
        (field (name "INTERNAL_PART_NUMBER") "MCD-00085")
        (field (name "MANUFACTURER") "STMICROELECTRONICS")
        (field (name "PROVIDED_BY") "Subcon")
      )
      (libsource (lib "MCD_PARTS_database") (part "STM32F103CBT6"))
    )
    (comp (ref "U3")
      (value "LD3985M33R")
      (footprint "REG_SOT23-5L")
      (description "Ultra low drop-low noise BiCMOS voltage, regulators low ESR capacitors compatible")
      (fields
        (field (name "INTERNAL_PART_NUMBER") "MCD-00086")
        (field (name "MANUFACTURER") "STMICROELECTRONICS")
        (field (name "PROVIDED_BY") "Subcon")
      )
      (libsource (lib "MCD_PARTS_database") (part "LD3985M33R"))
    )
    (comp (ref "U4")
      (value "TPS2041C")
      (footprint "MOS_SOT23-5L")
      (description "5V Power Switch, 0.85A, RDSon 130mOhm max, with active low enable pin")
      (fields
        (field (name "INTERNAL_PART_NUMBER") "MCD-01785")
        (field (name "MANUFACTURER_PART_NUMBER") "TPS2041CDBVT")
        (field (name "PROVIDED_BY") "SUBCO")
      )
      (libsource (lib "MCD_PARTS_database") (part "TPS2041C"))
    )
    (comp (ref "U100")
      (value "SN74LVC2T45DCUT")
      (footprint "ICC_VSSOP8_DCU_R-PDSO-G8_2X2P30_P050")
      (description "Dual bit dual supply bus transceiver")
      (fields
        (field (name "INTERNAL_PART_NUMBER") "MCD-00264")
        (field (name "MANUFACTURER") "TEXAS INSTRUMENTS")
        (field (name "PROVIDED_BY") "Subcon")
      )
      (libsource (lib "MCD_PARTS_database") (part "SN74LVC2T45DCUT"))
    )
    (comp (ref "X1")
      (value "NX3225GD-8.00M")
      (footprint "CRY_NX3225GD_2P")
      (description "Crystal 8Mhz, 8pF, -+50PPM, SMD")
      (fields
        (field (name "INTERNAL_PART_NUMBER") "MCD-00092")
        (field (name "MANUFACTURER_PART_NUMBER") "NX3225GD 8MHz EXS00A-CG04874")
        (field (name "PROVIDED_BY") "STM")
      )
      (libsource (lib "MCD_PARTS_database") (part "XTAL_2_PINS"))
    )
  )
  (nets
    (net (code "1") (name "/AIN_1") (class "Default")
      (node (ref "R1") (pin "2") (pinfunction "2_2") (pintype "passive"))
      (node (ref "R21") (pin "2") (pinfunction "2_2") (pintype "passive"))
      (node (ref "R22") (pin "2") (pinfunction "2_2") (pintype "passive"))
      (node (ref "U2") (pin "10") (pinfunction "PA0_10") (pintype "passive"))
    )
    (net (code "2") (name "/LED_STLINK") (class "Default")
      (node (ref "R13") (pin "2") (pinfunction "2_2") (pintype "passive"))
      (node (ref "R14") (pin "2") (pinfunction "2_2") (pintype "passive"))
      (node (ref "U2") (pin "30") (pinfunction "PA9_30") (pintype "passive"))
    )
    (net (code "3") (name "/MCO") (class "Default")
      (node (ref "C8") (pin "1") (pinfunction "1_1") (pintype "passive"))
      (node (ref "R19") (pin "2") (pinfunction "2_2") (pintype "passive"))
    )
    (net (code "4") (name "/NRST") (class "Default")
      (node (ref "JP3") (pin "2") (pinfunction "NO_2") (pintype "passive"))
    )
    (net (code "5") (name "/PWR_ENn") (class "Default")
      (node (ref "R23") (pin "2") (pinfunction "2_2") (pintype "passive"))
      (node (ref "U2") (pin "28") (pinfunction "PB15_28") (pintype "passive"))
      (node (ref "U4") (pin "4") (pinfunction "~{EN}_4") (pintype "passive"))
    )
    (net (code "6") (name "/STLINK_USB_D_N") (class "Default")
      (node (ref "CN1") (pin "2") (pinfunction "DM_2") (pintype "passive"))
      (node (ref "U1") (pin "1") (pinfunction "IO_1_1") (pintype "passive"))
      (node (ref "U1") (pin "6") (pinfunction "IO1_6") (pintype "passive"))
      (node (ref "U2") (pin "32") (pinfunction "PA11_32") (pintype "passive"))
    )
    (net (code "7") (name "/STLINK_USB_D_P") (class "Default")
      (node (ref "CN1") (pin "3") (pinfunction "DP_3") (pintype "passive"))
      (node (ref "R8") (pin "2") (pinfunction "2_2") (pintype "passive"))
      (node (ref "U1") (pin "3") (pinfunction "IO_2_3") (pintype "passive"))
      (node (ref "U1") (pin "4") (pinfunction "IO2_4") (pintype "passive"))
      (node (ref "U2") (pin "33") (pinfunction "PA12_33") (pintype "passive"))
    )
    (net (code "8") (name "/STLK_OSC_IN") (class "Default")
      (node (ref "C4") (pin "1") (pinfunction "1_1") (pintype "passive"))
      (node (ref "U2") (pin "5") (pinfunction "OSCIN_5") (pintype "passive"))
      (node (ref "X1") (pin "1") (pinfunction "X1_1") (pintype "passive"))
    )
    (net (code "9") (name "/STLK_OSC_OUT") (class "Default")
      (node (ref "C5") (pin "1") (pinfunction "1_1") (pintype "passive"))
      (node (ref "U2") (pin "6") (pinfunction "OSCOUT_6") (pintype "passive"))
      (node (ref "X1") (pin "2") (pinfunction "X2_2") (pintype "passive"))
    )
    (net (code "10") (name "/STLK_RST") (class "Default")
      (node (ref "C2") (pin "2") (pinfunction "2_2") (pintype "passive"))
      (node (ref "JP2") (pin "2") (pinfunction "NO_2") (pintype "passive"))
      (node (ref "U2") (pin "7") (pinfunction "NRST_7") (pintype "passive"))
    )
    (net (code "11") (name "/STM_JTCK") (class "Default")
      (node (ref "SB102") (pin "2") (pinfunction "2_2") (pintype "passive"))
      (node (ref "U2") (pin "37") (pinfunction "JTCK/SWCLK_37") (pintype "passive"))
    )
    (net (code "12") (name "/STM_JTMS") (class "Default")
      (node (ref "SB106") (pin "2") (pinfunction "2_2") (pintype "passive"))
      (node (ref "U2") (pin "34") (pinfunction "JTMS/SWDIO_34") (pintype "passive"))
    )
    (net (code "13") (name "/SWCLK") (class "Default")
      (node (ref "SB103") (pin "1") (pinfunction "1_1") (pintype "passive"))
    )
    (net (code "14") (name "/SWDIO") (class "Default")
      (node (ref "SB107") (pin "1") (pinfunction "1_1") (pintype "passive"))
    )
    (net (code "15") (name "/SWO") (class "Default")
      (node (ref "SB108") (pin "2") (pinfunction "2_2") (pintype "passive"))
      (node (ref "U100") (pin "6") (pinfunction "B2_6") (pintype "passive"))
    )
    (net (code "16") (name "/T_JTCK") (class "Default")
      (node (ref "R15") (pin "2") (pinfunction "2_2") (pintype "passive"))
      (node (ref "SB101") (pin "1") (pinfunction "1_1") (pintype "passive"))
      (node (ref "U2") (pin "15") (pinfunction "PA5_15") (pintype "passive"))
      (node (ref "U2") (pin "26") (pinfunction "PB13_26") (pintype "passive"))
    )
    (net (code "17") (name "/T_JTMS") (class "Default")
      (node (ref "R16") (pin "2") (pinfunction "2_2") (pintype "passive"))
      (node (ref "R24") (pin "2") (pinfunction "2_2") (pintype "passive"))
      (node (ref "SB105") (pin "1") (pinfunction "1_1") (pintype "passive"))
      (node (ref "U100") (pin "7") (pinfunction "B1_7") (pintype "passive"))
      (node (ref "U2") (pin "27") (pinfunction "PB14_27") (pintype "passive"))
    )
    (net (code "18") (name "/T_MCO") (class "Default")
      (node (ref "R19") (pin "1") (pinfunction "1_1") (pintype "passive"))
      (node (ref "U2") (pin "29") (pinfunction "PA8_29") (pintype "passive"))
    )
    (net (code "19") (name "/T_NRST") (class "Default")
      (node (ref "JP3") (pin "1") (pinfunction "COMMON_1") (pintype "passive"))
      (node (ref "R17") (pin "2") (pinfunction "2_2") (pintype "passive"))
      (node (ref "U2") (pin "18") (pinfunction "PB0_18") (pintype "passive"))
    )
    (net (code "20") (name "/T_SWDIO_IN") (class "Default")
      (node (ref "R24") (pin "1") (pinfunction "1_1") (pintype "passive"))
      (node (ref "U100") (pin "2") (pinfunction "A1_2") (pintype "passive"))
      (node (ref "U2") (pin "25") (pinfunction "PB12_25") (pintype "passive"))
    )
    (net (code "21") (name "/T_SWO") (class "Default")
      (node (ref "R18") (pin "2") (pinfunction "2_2") (pintype "passive"))
      (node (ref "SB108") (pin "1") (pinfunction "1_1") (pintype "passive"))
      (node (ref "U100") (pin "3") (pinfunction "A2_3") (pintype "passive"))
      (node (ref "U2") (pin "31") (pinfunction "PA10_31") (pintype "passive"))
    )
    (net (code "22") (name "/T_VCP_RX") (class "Default")
      (node (ref "CN6") (pin "1") (pinfunction "1_1") (pintype "passive"))
      (node (ref "U2") (pin "12") (pinfunction "PA2_12") (pintype "passive"))
    )
    (net (code "23") (name "/T_VCP_TX") (class "Default")
      (node (ref "CN6") (pin "2") (pinfunction "2_2") (pintype "passive"))
      (node (ref "U2") (pin "13") (pinfunction "PA3_13") (pintype "passive"))
    )
    (net (code "24") (name "/USB_RENUMn") (class "Default")
      (node (ref "R10") (pin "2") (pinfunction "2_2") (pintype "passive"))
      (node (ref "U2") (pin "38") (pinfunction "PA15/JTDI_38") (pintype "passive"))
    )
    (net (code "25") (name "3V3_PER") (class "Default")
      (node (ref "R21") (pin "1") (pinfunction "1_1") (pintype "passive"))
      (node (ref "SB110") (pin "2") (pinfunction "2_2") (pintype "passive"))
    )
    (net (code "26") (name "3V3_STLK") (class "Default")
      (node (ref "C1") (pin "2") (pinfunction "2_2") (pintype "passive"))
      (node (ref "C100") (pin "2") (pinfunction "2_2") (pintype "passive"))
      (node (ref "C13") (pin "2") (pinfunction "2_2") (pintype "passive"))
      (node (ref "C14") (pin "2") (pinfunction "2_2") (pintype "passive"))
      (node (ref "C3") (pin "2") (pinfunction "2_2") (pintype "passive"))
      (node (ref "C6") (pin "2") (pinfunction "2_2") (pintype "passive"))
      (node (ref "C7") (pin "2") (pinfunction "2_2") (pintype "passive"))
      (node (ref "LD4") (pin "4") (pinfunction "YellowGreen_anode_4") (pintype "passive"))
      (node (ref "Q1") (pin "3") (pinfunction "C_3") (pintype "passive"))
      (node (ref "SB1") (pin "1") (pinfunction "1_1") (pintype "passive"))
      (node (ref "SB100") (pin "2") (pinfunction "2_2") (pintype "passive"))
      (node (ref "TP2") (pin "1") (pinfunction "1_1") (pintype "passive"))
      (node (ref "U100") (pin "1") (pinfunction "VccA_1") (pintype "power_in"))
      (node (ref "U2") (pin "1") (pinfunction "VBAT_1") (pintype "passive"))
      (node (ref "U2") (pin "24") (pinfunction "VDD_1_24") (pintype "passive"))
      (node (ref "U2") (pin "36") (pinfunction "VDD_2_36") (pintype "passive"))
      (node (ref "U2") (pin "48") (pinfunction "VDD_3_48") (pintype "passive"))
      (node (ref "U2") (pin "9") (pinfunction "VDDA_9") (pintype "passive"))
      (node (ref "U3") (pin "5") (pinfunction "Vout_5") (pintype "passive"))
    )
    (net (code "27") (name "5V") (class "Default")
      (node (ref "D2") (pin "1") (pinfunction "A_1") (pintype "passive"))
    )
    (net (code "28") (name "5V_EXT") (class "Default")
      (node (ref "D4") (pin "1") (pinfunction "A_1") (pintype "passive"))
    )
    (net (code "29") (name "5V_STLK") (class "Default")
      (node (ref "C11") (pin "2") (pinfunction "2_2") (pintype "passive"))
      (node (ref "TP3") (pin "1") (pinfunction "1_1") (pintype "passive"))
      (node (ref "U4") (pin "1") (pinfunction "OUT_1") (pintype "passive"))
    )
    (net (code "30") (name "5V_UCPD") (class "Default")
      (node (ref "D3") (pin "1") (pinfunction "A_1") (pintype "passive"))
    )
    (net (code "31") (name "5V_USB_STLK") (class "Default")
      (node (ref "C12") (pin "2") (pinfunction "2_2") (pintype "passive"))
      (node (ref "CN1") (pin "1") (pinfunction "VBUS_1") (pintype "passive"))
      (node (ref "D6") (pin "1") (pinfunction "A_1") (pintype "passive"))
      (node (ref "R12") (pin "1") (pinfunction "1_1") (pintype "passive"))
      (node (ref "R20") (pin "1") (pinfunction "1_1") (pintype "passive"))
      (node (ref "R23") (pin "1") (pinfunction "1_1") (pintype "passive"))
      (node (ref "TP1") (pin "1") (pinfunction "1_1") (pintype "passive"))
      (node (ref "U1") (pin "5") (pinfunction "VBUS_5") (pintype "passive"))
      (node (ref "U4") (pin "5") (pinfunction "IN_5") (pintype "passive"))
    )
    (net (code "32") (name "5V_VIN") (class "Default")
      (node (ref "D5") (pin "1") (pinfunction "A_1") (pintype "passive"))
    )
    (net (code "33") (name "GND") (class "Default")
      (node (ref "C1") (pin "1") (pinfunction "1_1") (pintype "passive"))
      (node (ref "C10") (pin "1") (pinfunction "1_1") (pintype "passive"))
      (node (ref "C100") (pin "1") (pinfunction "1_1") (pintype "passive"))
      (node (ref "C101") (pin "2") (pinfunction "2_2") (pintype "passive"))
      (node (ref "C11") (pin "1") (pinfunction "1_1") (pintype "passive"))
      (node (ref "C12") (pin "1") (pinfunction "1_1") (pintype "passive"))
      (node (ref "C13") (pin "1") (pinfunction "1_1") (pintype "passive"))
      (node (ref "C14") (pin "1") (pinfunction "1_1") (pintype "passive"))
      (node (ref "C15") (pin "1") (pinfunction "1_1") (pintype "passive"))
      (node (ref "C2") (pin "1") (pinfunction "1_1") (pintype "passive"))
      (node (ref "C3") (pin "1") (pinfunction "1_1") (pintype "passive"))
      (node (ref "C4") (pin "2") (pinfunction "2_2") (pintype "passive"))
      (node (ref "C5") (pin "2") (pinfunction "2_2") (pintype "passive"))
      (node (ref "C6") (pin "1") (pinfunction "1_1") (pintype "passive"))
      (node (ref "C7") (pin "1") (pinfunction "1_1") (pintype "passive"))
      (node (ref "C8") (pin "2") (pinfunction "2_2") (pintype "passive"))
      (node (ref "C9") (pin "1") (pinfunction "1_1") (pintype "passive"))
      (node (ref "CN1") (pin "10") (pinfunction "EXP_10") (pintype "passive"))
      (node (ref "CN1") (pin "11") (pinfunction "EXP_11") (pintype "passive"))
      (node (ref "CN1") (pin "5") (pinfunction "GND_5") (pintype "passive"))
      (node (ref "CN1") (pin "6") (pinfunction "Shield_6") (pintype "passive"))
      (node (ref "CN1") (pin "7") (pinfunction "Shield_7") (pintype "passive"))
      (node (ref "CN1") (pin "8") (pinfunction "Shield_8") (pintype "passive"))
      (node (ref "CN1") (pin "9") (pinfunction "Shield_9") (pintype "passive"))
      (node (ref "CN2") (pin "1") (pinfunction "COMMON_1") (pintype "passive"))
      (node (ref "CN2") (pin "2") (pinfunction "NO_2") (pintype "passive"))
      (node (ref "CN3") (pin "1") (pinfunction "COMMON_1") (pintype "passive"))
      (node (ref "CN3") (pin "2") (pinfunction "NO_2") (pintype "passive"))
      (node (ref "CN5") (pin "3") (pinfunction "3_3") (pintype "passive"))
      (node (ref "JP2") (pin "1") (pinfunction "COMMON_1") (pintype "passive"))
      (node (ref "LD4") (pin "1") (pinfunction "RED_cathode_1") (pintype "passive"))
      (node (ref "R11") (pin "1") (pinfunction "1_1") (pintype "passive"))
      (node (ref "R2") (pin "1") (pinfunction "1_1") (pintype "passive"))
      (node (ref "R22") (pin "1") (pinfunction "1_1") (pintype "passive"))
      (node (ref "R3") (pin "1") (pinfunction "1_1") (pintype "passive"))
      (node (ref "R4") (pin "1") (pinfunction "1_1") (pintype "passive"))
      (node (ref "R5") (pin "2") (pinfunction "2_2") (pintype "passive"))
      (node (ref "R7") (pin "1") (pinfunction "1_1") (pintype "passive"))
      (node (ref "R9") (pin "2") (pinfunction "2_2") (pintype "passive"))
      (node (ref "SB104") (pin "2") (pinfunction "2_2") (pintype "passive"))
      (node (ref "U1") (pin "2") (pinfunction "GND_2") (pintype "passive"))
      (node (ref "U100") (pin "4") (pinfunction "GND_4") (pintype "power_in"))
      (node (ref "U100") (pin "5") (pinfunction "DIR_5") (pintype "passive"))
      (node (ref "U2") (pin "20") (pinfunction "PB2/BOOT1_20") (pintype "passive"))
      (node (ref "U2") (pin "23") (pinfunction "VSS_1_23") (pintype "passive"))
      (node (ref "U2") (pin "35") (pinfunction "VSS_2_35") (pintype "passive"))
      (node (ref "U2") (pin "47") (pinfunction "VSS_3_47") (pintype "passive"))
      (node (ref "U2") (pin "8") (pinfunction "VSSA_8") (pintype "passive"))
      (node (ref "U3") (pin "2") (pinfunction "GND_2") (pintype "passive"))
      (node (ref "U4") (pin "2") (pinfunction "GND_2") (pintype "passive"))
    )
    (net (code "34") (name "Net-(CN1-ID)") (class "Default")
      (node (ref "CN1") (pin "4") (pinfunction "ID_4") (pintype "passive"))
      (node (ref "R7") (pin "2") (pinfunction "2_2") (pintype "passive"))
    )
    (net (code "35") (name "Net-(CN4-Pad1)") (class "Default")
      (node (ref "CN4") (pin "1") (pinfunction "1_1") (pintype "passive"))
      (node (ref "SB100") (pin "1") (pinfunction "1_1") (pintype "passive"))
      (node (ref "SB101") (pin "2") (pinfunction "2_2") (pintype "passive"))
    )
    (net (code "36") (name "Net-(CN4-Pad2)") (class "Default")
      (node (ref "CN4") (pin "2") (pinfunction "2_2") (pintype "passive"))
      (node (ref "SB102") (pin "1") (pinfunction "1_1") (pintype "passive"))
      (node (ref "SB103") (pin "2") (pinfunction "2_2") (pintype "passive"))
    )
    (net (code "37") (name "Net-(CN4-Pad3)") (class "Default")
      (node (ref "CN4") (pin "3") (pinfunction "3_3") (pintype "passive"))
      (node (ref "SB104") (pin "1") (pinfunction "1_1") (pintype "passive"))
      (node (ref "SB105") (pin "2") (pinfunction "2_2") (pintype "passive"))
    )
    (net (code "38") (name "Net-(CN4-Pad4)") (class "Default")
      (node (ref "CN4") (pin "4") (pinfunction "4_4") (pintype "passive"))
      (node (ref "SB106") (pin "1") (pinfunction "1_1") (pintype "passive"))
      (node (ref "SB107") (pin "2") (pinfunction "2_2") (pintype "passive"))
    )
    (net (code "39") (name "Net-(CN5-Pad2)") (class "Default")
      (node (ref "CN5") (pin "2") (pinfunction "2_2") (pintype "passive"))
      (node (ref "R15") (pin "1") (pinfunction "1_1") (pintype "passive"))
    )
    (net (code "40") (name "Net-(CN5-Pad4)") (class "Default")
      (node (ref "CN5") (pin "4") (pinfunction "4_4") (pintype "passive"))
      (node (ref "R16") (pin "1") (pinfunction "1_1") (pintype "passive"))
    )
    (net (code "41") (name "Net-(CN5-Pad5)") (class "Default")
      (node (ref "CN5") (pin "5") (pinfunction "5_5") (pintype "passive"))
      (node (ref "R17") (pin "1") (pinfunction "1_1") (pintype "passive"))
    )
    (net (code "42") (name "Net-(CN5-Pad6)") (class "Default")
      (node (ref "CN5") (pin "6") (pinfunction "6_6") (pintype "passive"))
      (node (ref "R18") (pin "1") (pinfunction "1_1") (pintype "passive"))
    )
    (net (code "43") (name "Net-(D1-A)") (class "Default")
      (node (ref "CN5") (pin "1") (pinfunction "1_1") (pintype "passive"))
      (node (ref "D1") (pin "1") (pinfunction "A_1") (pintype "passive"))
      (node (ref "R9") (pin "1") (pinfunction "1_1") (pintype "passive"))
    )
    (net (code "44") (name "Net-(D1-K)") (class "Default")
      (node (ref "D1") (pin "2") (pinfunction "K_2") (pintype "passive"))
      (node (ref "R1") (pin "1") (pinfunction "1_1") (pintype "passive"))
    )
    (net (code "45") (name "Net-(D2-K)") (class "Default")
      (node (ref "D2") (pin "2") (pinfunction "K_2") (pintype "passive"))
      (node (ref "R6") (pin "1") (pinfunction "1_1") (pintype "passive"))
    )
    (net (code "46") (name "Net-(D3-K)") (class "Default")
      (node (ref "C15") (pin "2") (pinfunction "2_2") (pintype "passive"))
      (node (ref "C9") (pin "2") (pinfunction "2_2") (pintype "passive"))
      (node (ref "D3") (pin "2") (pinfunction "K_2") (pintype "passive"))
      (node (ref "D4") (pin "2") (pinfunction "K_2") (pintype "passive"))
      (node (ref "D5") (pin "2") (pinfunction "K_2") (pintype "passive"))
      (node (ref "D6") (pin "2") (pinfunction "K_2") (pintype "passive"))
      (node (ref "U3") (pin "1") (pinfunction "Vin_1") (pintype "passive"))
      (node (ref "U3") (pin "3") (pinfunction "CE_3") (pintype "passive"))
    )
    (net (code "47") (name "Net-(LD4-Red_anode)") (class "Default")
      (node (ref "LD4") (pin "2") (pinfunction "Red_anode_2") (pintype "passive"))
      (node (ref "R14") (pin "1") (pinfunction "1_1") (pintype "passive"))
    )
    (net (code "48") (name "Net-(LD4-YellowGreen_cathode)") (class "Default")
      (node (ref "LD4") (pin "3") (pinfunction "YellowGreen_cathode_3") (pintype "passive"))
      (node (ref "R13") (pin "1") (pinfunction "1_1") (pintype "passive"))
    )
    (net (code "49") (name "Net-(LD5-Pad1)") (class "Default")
      (node (ref "LD5") (pin "1") (pintype "passive"))
      (node (ref "R20") (pin "2") (pinfunction "2_2") (pintype "passive"))
    )
    (net (code "50") (name "Net-(Q1-B)") (class "Default")
      (node (ref "Q1") (pin "1") (pinfunction "B_1") (pintype "passive"))
      (node (ref "R10") (pin "1") (pinfunction "1_1") (pintype "passive"))
      (node (ref "R11") (pin "2") (pinfunction "2_2") (pintype "passive"))
      (node (ref "R12") (pin "2") (pinfunction "2_2") (pintype "passive"))
    )
    (net (code "51") (name "Net-(Q1-E)") (class "Default")
      (node (ref "Q1") (pin "2") (pinfunction "E_2") (pintype "passive"))
      (node (ref "R8") (pin "1") (pinfunction "1_1") (pintype "passive"))
    )
    (net (code "52") (name "Net-(U2-BOOT0)") (class "Default")
      (node (ref "R4") (pin "2") (pinfunction "2_2") (pintype "passive"))
      (node (ref "U2") (pin "44") (pinfunction "BOOT0_44") (pintype "passive"))
    )
    (net (code "53") (name "Net-(U2-PB3{slash}JTDO)") (class "Default")
      (node (ref "R5") (pin "1") (pinfunction "1_1") (pintype "passive"))
      (node (ref "R6") (pin "2") (pinfunction "2_2") (pintype "passive"))
      (node (ref "SB1") (pin "2") (pinfunction "2_2") (pintype "passive"))
      (node (ref "U2") (pin "39") (pinfunction "PB3/JTDO_39") (pintype "passive"))
    )
    (net (code "54") (name "Net-(U2-PC13)") (class "Default")
      (node (ref "R3") (pin "2") (pinfunction "2_2") (pintype "passive"))
      (node (ref "U2") (pin "2") (pinfunction "PC13_2") (pintype "passive"))
    )
    (net (code "55") (name "Net-(U2-PC14)") (class "Default")
      (node (ref "R2") (pin "2") (pinfunction "2_2") (pintype "passive"))
      (node (ref "U2") (pin "3") (pinfunction "PC14_3") (pintype "passive"))
    )
    (net (code "56") (name "Net-(U3-BYPASS)") (class "Default")
      (node (ref "C10") (pin "2") (pinfunction "2_2") (pintype "passive"))
      (node (ref "U3") (pin "4") (pinfunction "BYPASS_4") (pintype "passive"))
    )
    (net (code "57") (name "Net-(U4-~{FAULT})") (class "Default")
      (node (ref "LD5") (pin "2") (pintype "passive"))
      (node (ref "U4") (pin "3") (pinfunction "~{FAULT}_3") (pintype "passive"))
    )
    (net (code "58") (name "Net-(U100-VccB)") (class "Default")
      (node (ref "C101") (pin "1") (pinfunction "1_1") (pintype "passive"))
      (node (ref "SB109") (pin "1") (pinfunction "1_1") (pintype "passive"))
      (node (ref "SB110") (pin "1") (pinfunction "1_1") (pintype "passive"))
      (node (ref "U100") (pin "8") (pinfunction "VccB_8") (pintype "power_in"))
    )
    (net (code "59") (name "VDD_MCU") (class "Default")
      (node (ref "SB109") (pin "2") (pinfunction "2_2") (pintype "passive"))
    )
    (net (code "60") (name "unconnected-(U2-PA1-Pad11)") (class "Default")
      (node (ref "U2") (pin "11") (pinfunction "PA1_11") (pintype "passive+no_connect"))
    )
    (net (code "61") (name "unconnected-(U2-PA4-Pad14)") (class "Default")
      (node (ref "U2") (pin "14") (pinfunction "PA4_14") (pintype "passive+no_connect"))
    )
    (net (code "62") (name "unconnected-(U2-PA6-Pad16)") (class "Default")
      (node (ref "U2") (pin "16") (pinfunction "PA6_16") (pintype "passive+no_connect"))
    )
    (net (code "63") (name "unconnected-(U2-PA7-Pad17)") (class "Default")
      (node (ref "U2") (pin "17") (pinfunction "PA7_17") (pintype "passive+no_connect"))
    )
    (net (code "64") (name "unconnected-(U2-PB1-Pad19)") (class "Default")
      (node (ref "U2") (pin "19") (pinfunction "PB1_19") (pintype "passive+no_connect"))
    )
    (net (code "65") (name "unconnected-(U2-PB4{slash}JNTRST-Pad40)") (class "Default")
      (node (ref "U2") (pin "40") (pinfunction "PB4/JNTRST_40") (pintype "passive+no_connect"))
    )
    (net (code "66") (name "unconnected-(U2-PB5-Pad41)") (class "Default")
      (node (ref "U2") (pin "41") (pinfunction "PB5_41") (pintype "passive+no_connect"))
    )
    (net (code "67") (name "unconnected-(U2-PB6-Pad42)") (class "Default")
      (node (ref "U2") (pin "42") (pinfunction "PB6_42") (pintype "passive+no_connect"))
    )
    (net (code "68") (name "unconnected-(U2-PB7-Pad43)") (class "Default")
      (node (ref "U2") (pin "43") (pinfunction "PB7_43") (pintype "passive+no_connect"))
    )
    (net (code "69") (name "unconnected-(U2-PB8-Pad45)") (class "Default")
      (node (ref "U2") (pin "45") (pinfunction "PB8_45") (pintype "passive+no_connect"))
    )
    (net (code "70") (name "unconnected-(U2-PB9-Pad46)") (class "Default")
      (node (ref "U2") (pin "46") (pinfunction "PB9_46") (pintype "passive+no_connect"))
    )
    (net (code "71") (name "unconnected-(U2-PB10-Pad21)") (class "Default")
      (node (ref "U2") (pin "21") (pinfunction "PB10_21") (pintype "passive+no_connect"))
    )
    (net (code "72") (name "unconnected-(U2-PB11-Pad22)") (class "Default")
      (node (ref "U2") (pin "22") (pinfunction "PB11_22") (pintype "passive+no_connect"))
    )
    (net (code "73") (name "unconnected-(U2-PC15-Pad4)") (class "Default")
      (node (ref "U2") (pin "4") (pinfunction "PC15_4") (pintype "passive+no_connect"))
    )
  )
)
